# 04-ZYNQ_BANK_501.net
KiCad netlist of a schematic drawn in Altium Designer
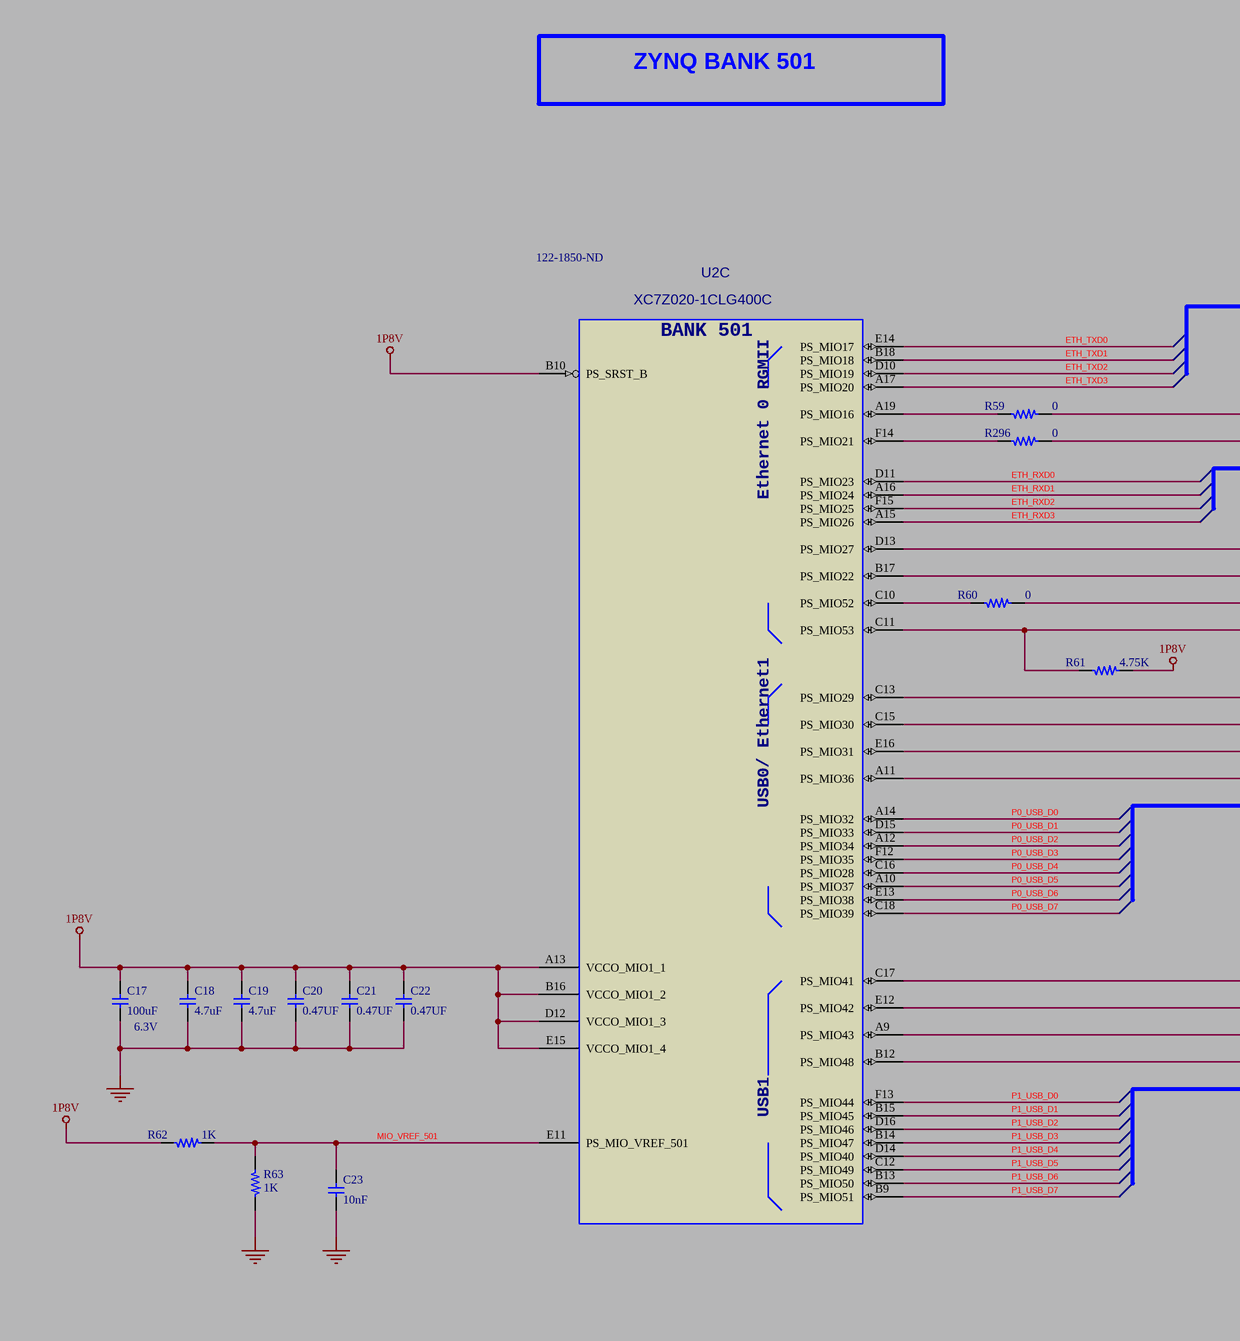
[diagram p0: 04-ZYNQ BANK 501.SchDoc, left]
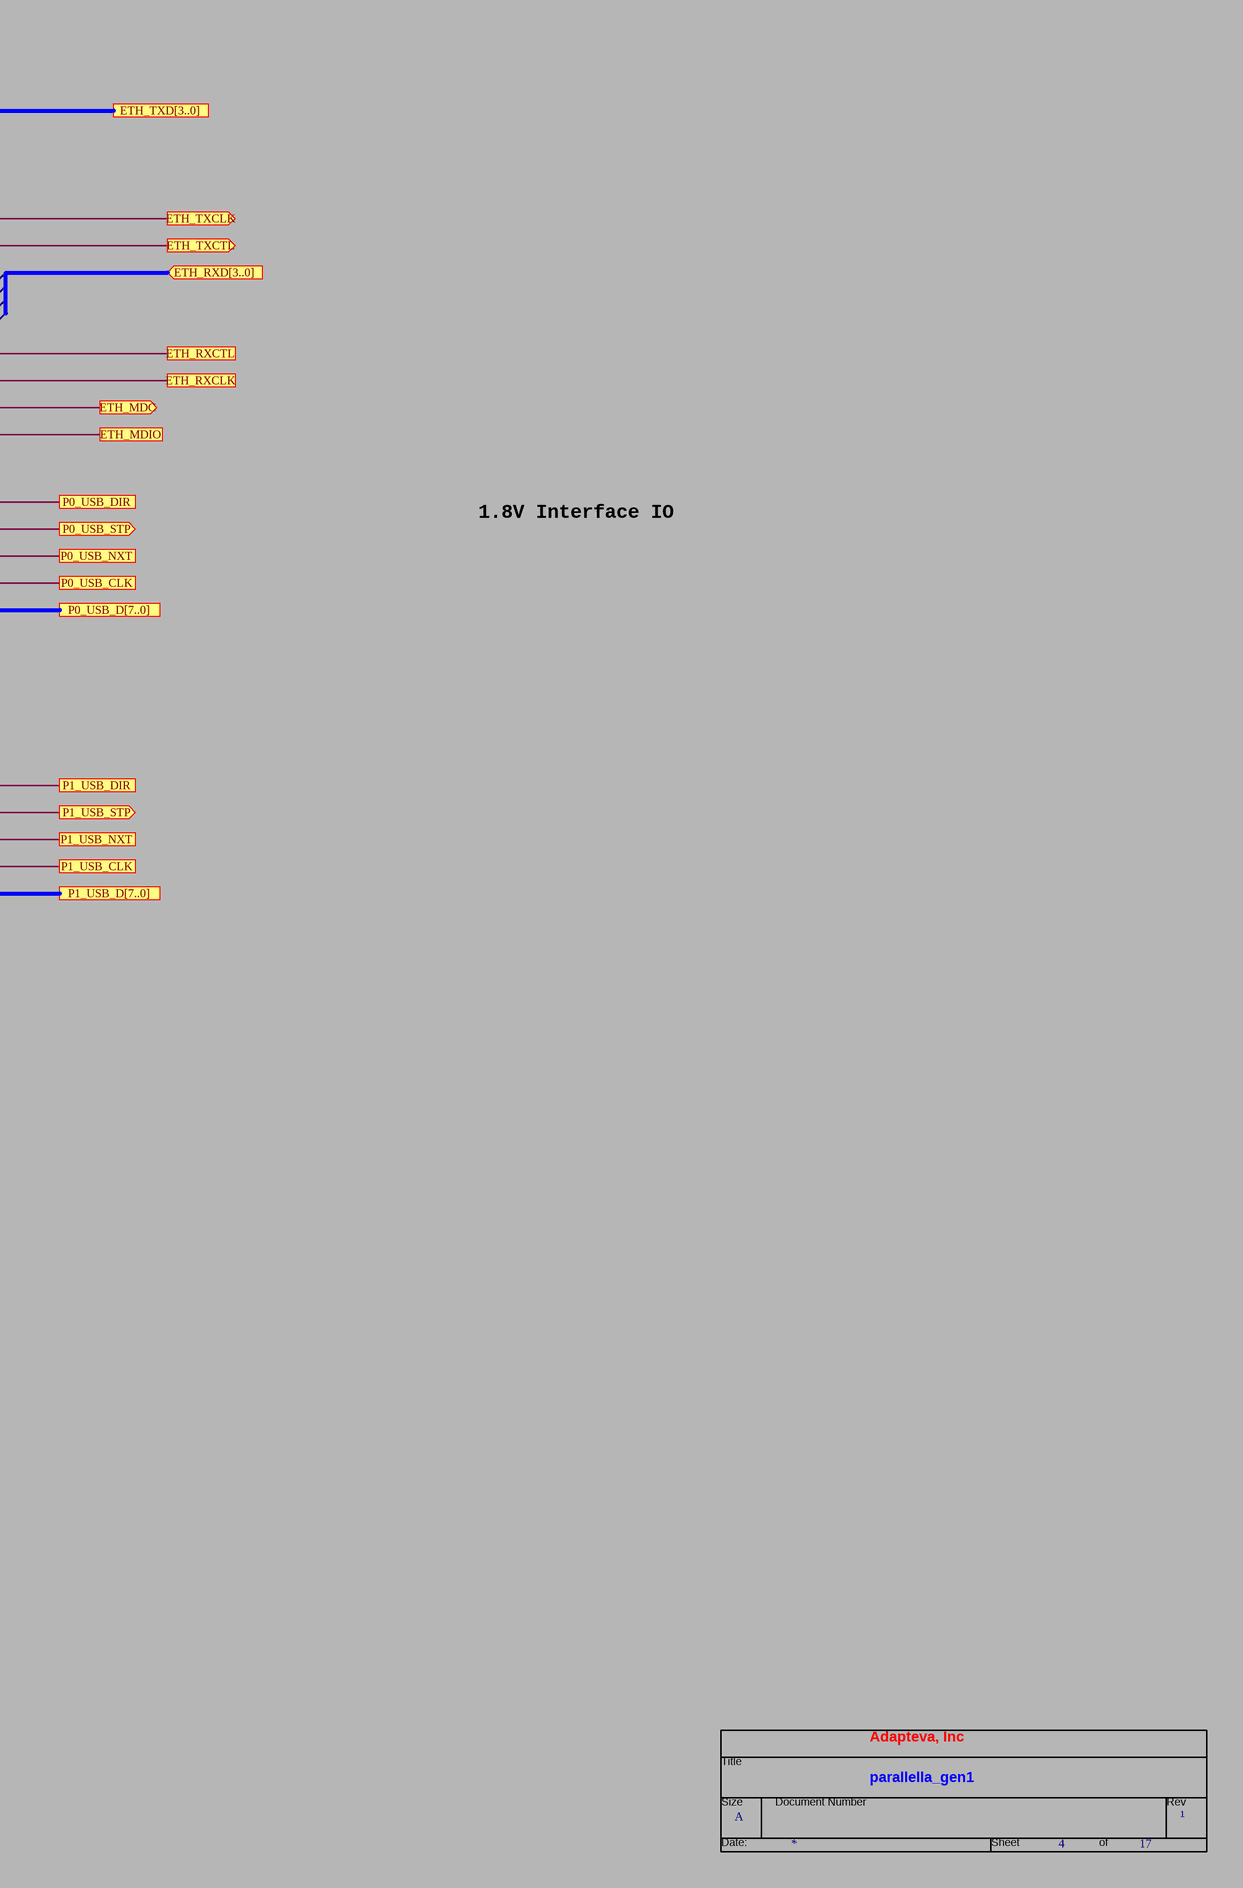
[diagram p1: 04-ZYNQ BANK 501.SchDoc, right]

(export (version "E")
  (design (tool "Eeschema 10.0.6"))
  (components
    (comp (ref "C17")
      (value "100uF")
      (footprint "C1210")
      (description "CAP, 1210, 100UF, X5R, 6.3V, LOW ESR")
      (fields
        (field (name "VOLTAGE") "6.3V")
        (field (name "MFG PART NO") "GRM32ER60J107ME20L")
        (field (name "MFG") "MURATA")
      )
      (libsource (lib "*") (part "CAP1210_100UF_X5R_LOESR"))
    )
    (comp (ref "C18")
      (value "4.7uF")
      (footprint "C0402")
      (description "CAP, 0402, 4.7UF, X5R, 6.3V")
      (fields (field (name "MFG PART NO") "C1005X5R0J475K") (field (name "MFG") "TDK"))
      (libsource (lib "*") (part "CAP0402_4P7UF_X5R"))
    )
    (comp (ref "C19")
      (value "4.7uF")
      (footprint "C0402")
      (description "CAP, 0402, 4.7UF, X5R, 6.3V")
      (fields (field (name "MFG PART NO") "C1005X5R0J475K") (field (name "MFG") "TDK"))
      (libsource (lib "*") (part "CAP0402_4P7UF_X5R"))
    )
    (comp (ref "C20")
      (value "0.47UF")
      (footprint "C0402")
      (description "CAP, 0402, 0.47UF, X5R, 16V")
      (fields (field (name "MFG") "TDK") (field (name "MFG PART NO") "C1005X5R1C474K"))
      (libsource (lib "*") (part "CAP0402_0P47UF_X5R"))
    )
    (comp (ref "C21")
      (value "0.47UF")
      (footprint "C0402")
      (description "CAP, 0402, 0.47UF, X5R, 16V")
      (fields (field (name "MFG") "TDK") (field (name "MFG PART NO") "C1005X5R1C474K"))
      (libsource (lib "*") (part "CAP0402_0P47UF_X5R"))
    )
    (comp (ref "C22")
      (value "0.47UF")
      (footprint "C0402")
      (description "CAP, 0402, 0.47UF, X5R, 16V")
      (fields (field (name "MFG") "TDK") (field (name "MFG PART NO") "C1005X5R1C474K"))
      (libsource (lib "*") (part "CAP0402_0P47UF_X5R"))
    )
    (comp (ref "C23")
      (value "10nF")
      (footprint "C0402")
      (description "CAP, 0402, 10NF, X7R, 16V")
      (fields (field (name "MFG") "TDK") (field (name "MFG PART NO") "C1005X7R1C103K"))
      (libsource (lib "*") (part "CAP0402_10NF_X7R_16V"))
    )
    (comp (ref "R59")
      (value "0")
      (footprint "R0402")
      (description "RES, 0402, 0 OHM, 1%")
      (fields (field (name "MFG") "VISHAY") (field (name "MFG PART NO") "CRCW04020000Z0ED"))
      (libsource (lib "*") (part "RES0402_0"))
    )
    (comp (ref "R60")
      (value "0")
      (footprint "R0402")
      (description "RES, 0402, 0 OHM, 1%")
      (fields (field (name "MFG") "VISHAY") (field (name "MFG PART NO") "CRCW04020000Z0ED"))
      (libsource (lib "*") (part "RES0402_0"))
    )
    (comp (ref "R61")
      (value "4.75K")
      (footprint "R0402")
      (description "RES, 0402, 4.75K, 1%")
      (fields (field (name "MFG") "VISHAY") (field (name "MFG PART NO") "CRCW04024K75FKED"))
      (libsource (lib "*") (part "RES0402_4K75"))
    )
    (comp (ref "R62")
      (value "1K")
      (footprint "R0402")
      (description "RES, 0402, 1K")
      (fields (field (name "MFG") "VISHAY") (field (name "MFG PART NO") "CRCW04021K00FKED"))
      (libsource (lib "*") (part "RES0402_1K"))
    )
    (comp (ref "R63")
      (value "1K")
      (footprint "R0402")
      (description "RES, 0402, 1K")
      (fields (field (name "MFG") "VISHAY") (field (name "MFG PART NO") "CRCW04021K00FKED"))
      (libsource (lib "*") (part "RES0402_1K"))
    )
    (comp (ref "R296")
      (value "0")
      (footprint "R0402")
      (description "RES, 0402, 0 OHM, 1%")
      (fields (field (name "MFG") "VISHAY") (field (name "MFG PART NO") "CRCW04020000Z0ED"))
      (libsource (lib "*") (part "RES0402_0"))
    )
    (comp (ref "U2")
      (value "7Z020-CLG400")
      (footprint "CBGA400_17SQ_1P6H_P8MMP")
      (description "IC, EPP, XILINX, ZYNQ, 7Z020, CLG400")
      (fields
        (field (name "VENDOR PN") "XC7Z020-1CLG400C")
        (field (name "SUPPLIER PART NUMBER 1") "122-1850-ND")
      )
      (libsource (lib "*") (part "ZYNQ_7Z020_CLG400"))
    )
  )
  (nets
    (net (code "1") (name "/ETH_MDC") (class "Default")
      (node (ref "R60") (pin "2") (pinfunction "2_2") (pintype "passive"))
    )
    (net (code "2") (name "/ETH_MDIO") (class "Default")
      (node (ref "R61") (pin "1") (pinfunction "1_1") (pintype "passive"))
      (node (ref "U2") (pin "C11") (pinfunction "PS_MIO53_C11") (pintype "bidirectional"))
    )
    (net (code "3") (name "/ETH_RXCLK") (class "Default")
      (node (ref "U2") (pin "B17") (pinfunction "PS_MIO22_B17") (pintype "bidirectional"))
    )
    (net (code "4") (name "/ETH_RXCTL") (class "Default")
      (node (ref "U2") (pin "D13") (pinfunction "PS_MIO27_D13") (pintype "bidirectional"))
    )
    (net (code "5") (name "/ETH_RXD0") (class "Default")
      (node (ref "U2") (pin "D11") (pinfunction "PS_MIO23_D11") (pintype "bidirectional"))
    )
    (net (code "6") (name "/ETH_RXD1") (class "Default")
      (node (ref "U2") (pin "A16") (pinfunction "PS_MIO24_A16") (pintype "bidirectional"))
    )
    (net (code "7") (name "/ETH_RXD2") (class "Default")
      (node (ref "U2") (pin "F15") (pinfunction "PS_MIO25_F15") (pintype "bidirectional"))
    )
    (net (code "8") (name "/ETH_RXD3") (class "Default")
      (node (ref "U2") (pin "A15") (pinfunction "PS_MIO26_A15") (pintype "bidirectional"))
    )
    (net (code "10") (name "/ETH_TXCLK") (class "Default")
      (node (ref "R59") (pin "2") (pinfunction "2_2") (pintype "passive"))
    )
    (net (code "11") (name "/ETH_TXCTL") (class "Default")
      (node (ref "R296") (pin "2") (pinfunction "2_2") (pintype "passive"))
    )
    (net (code "12") (name "/ETH_TXD0") (class "Default")
      (node (ref "U2") (pin "E14") (pinfunction "PS_MIO17_E14") (pintype "bidirectional"))
    )
    (net (code "13") (name "/ETH_TXD1") (class "Default")
      (node (ref "U2") (pin "B18") (pinfunction "PS_MIO18_B18") (pintype "bidirectional"))
    )
    (net (code "14") (name "/ETH_TXD2") (class "Default")
      (node (ref "U2") (pin "D10") (pinfunction "PS_MIO19_D10") (pintype "bidirectional"))
    )
    (net (code "15") (name "/ETH_TXD3") (class "Default")
      (node (ref "U2") (pin "A17") (pinfunction "PS_MIO20_A17") (pintype "bidirectional"))
    )
    (net (code "17") (name "/MIO_VREF_501") (class "Default")
      (node (ref "C23") (pin "1") (pinfunction "1_1") (pintype "passive"))
      (node (ref "R62") (pin "2") (pinfunction "2_2") (pintype "passive"))
      (node (ref "R63") (pin "1") (pinfunction "1_1") (pintype "passive"))
      (node (ref "U2") (pin "E11") (pinfunction "PS_MIO_VREF_501_E11") (pintype "power_in"))
    )
    (net (code "18") (name "/P0_USB_CLK") (class "Default")
      (node (ref "U2") (pin "A11") (pinfunction "PS_MIO36_A11") (pintype "bidirectional"))
    )
    (net (code "19") (name "/P0_USB_D0") (class "Default")
      (node (ref "U2") (pin "A14") (pinfunction "PS_MIO32_A14") (pintype "bidirectional"))
    )
    (net (code "20") (name "/P0_USB_D1") (class "Default")
      (node (ref "U2") (pin "D15") (pinfunction "PS_MIO33_D15") (pintype "bidirectional"))
    )
    (net (code "21") (name "/P0_USB_D2") (class "Default")
      (node (ref "U2") (pin "A12") (pinfunction "PS_MIO34_A12") (pintype "bidirectional"))
    )
    (net (code "22") (name "/P0_USB_D3") (class "Default")
      (node (ref "U2") (pin "F12") (pinfunction "PS_MIO35_F12") (pintype "bidirectional"))
    )
    (net (code "23") (name "/P0_USB_D4") (class "Default")
      (node (ref "U2") (pin "C16") (pinfunction "PS_MIO28_C16") (pintype "bidirectional"))
    )
    (net (code "24") (name "/P0_USB_D5") (class "Default")
      (node (ref "U2") (pin "A10") (pinfunction "PS_MIO37_A10") (pintype "bidirectional"))
    )
    (net (code "25") (name "/P0_USB_D6") (class "Default")
      (node (ref "U2") (pin "E13") (pinfunction "PS_MIO38_E13") (pintype "bidirectional"))
    )
    (net (code "26") (name "/P0_USB_D7") (class "Default")
      (node (ref "U2") (pin "C18") (pinfunction "PS_MIO39_C18") (pintype "bidirectional"))
    )
    (net (code "27") (name "/P0_USB_DIR") (class "Default")
      (node (ref "U2") (pin "C13") (pinfunction "PS_MIO29_C13") (pintype "bidirectional"))
    )
    (net (code "29") (name "/P0_USB_NXT") (class "Default")
      (node (ref "U2") (pin "E16") (pinfunction "PS_MIO31_E16") (pintype "bidirectional"))
    )
    (net (code "30") (name "/P0_USB_STP") (class "Default")
      (node (ref "U2") (pin "C15") (pinfunction "PS_MIO30_C15") (pintype "bidirectional"))
    )
    (net (code "31") (name "/P1_USB_CLK") (class "Default")
      (node (ref "U2") (pin "B12") (pinfunction "PS_MIO48_B12") (pintype "bidirectional"))
    )
    (net (code "32") (name "/P1_USB_D0") (class "Default")
      (node (ref "U2") (pin "F13") (pinfunction "PS_MIO44_F13") (pintype "bidirectional"))
    )
    (net (code "33") (name "/P1_USB_D1") (class "Default")
      (node (ref "U2") (pin "B15") (pinfunction "PS_MIO45_B15") (pintype "bidirectional"))
    )
    (net (code "34") (name "/P1_USB_D2") (class "Default")
      (node (ref "U2") (pin "D16") (pinfunction "PS_MIO46_D16") (pintype "bidirectional"))
    )
    (net (code "35") (name "/P1_USB_D3") (class "Default")
      (node (ref "U2") (pin "B14") (pinfunction "PS_MIO47_B14") (pintype "bidirectional"))
    )
    (net (code "36") (name "/P1_USB_D4") (class "Default")
      (node (ref "U2") (pin "D14") (pinfunction "PS_MIO40_D14") (pintype "bidirectional"))
    )
    (net (code "37") (name "/P1_USB_D5") (class "Default")
      (node (ref "U2") (pin "C12") (pinfunction "PS_MIO49_C12") (pintype "bidirectional"))
    )
    (net (code "38") (name "/P1_USB_D6") (class "Default")
      (node (ref "U2") (pin "B13") (pinfunction "PS_MIO50_B13") (pintype "bidirectional"))
    )
    (net (code "39") (name "/P1_USB_D7") (class "Default")
      (node (ref "U2") (pin "B9") (pinfunction "PS_MIO51_B9") (pintype "bidirectional"))
    )
    (net (code "40") (name "/P1_USB_DIR") (class "Default")
      (node (ref "U2") (pin "C17") (pinfunction "PS_MIO41_C17") (pintype "bidirectional"))
    )
    (net (code "42") (name "/P1_USB_NXT") (class "Default")
      (node (ref "U2") (pin "A9") (pinfunction "PS_MIO43_A9") (pintype "bidirectional"))
    )
    (net (code "43") (name "/P1_USB_STP") (class "Default")
      (node (ref "U2") (pin "E12") (pinfunction "PS_MIO42_E12") (pintype "bidirectional"))
    )
    (net (code "44") (name "1P8V") (class "Default")
      (node (ref "C17") (pin "1") (pinfunction "1_1") (pintype "passive"))
      (node (ref "C18") (pin "1") (pinfunction "1_1") (pintype "passive"))
      (node (ref "C19") (pin "1") (pinfunction "1_1") (pintype "passive"))
      (node (ref "C20") (pin "1") (pinfunction "1_1") (pintype "passive"))
      (node (ref "C21") (pin "1") (pinfunction "1_1") (pintype "passive"))
      (node (ref "C22") (pin "1") (pinfunction "1_1") (pintype "passive"))
      (node (ref "R61") (pin "2") (pinfunction "2_2") (pintype "passive"))
      (node (ref "R62") (pin "1") (pinfunction "1_1") (pintype "passive"))
      (node (ref "U2") (pin "A13") (pinfunction "VCCO_MIO1_1_A13") (pintype "power_in"))
      (node (ref "U2") (pin "B10") (pinfunction "PS_SRST_B_B10") (pintype "input"))
      (node (ref "U2") (pin "B16") (pinfunction "VCCO_MIO1_2_B16") (pintype "power_in"))
      (node (ref "U2") (pin "D12") (pinfunction "VCCO_MIO1_3_D12") (pintype "power_in"))
      (node (ref "U2") (pin "E15") (pinfunction "VCCO_MIO1_4_E15") (pintype "power_in"))
    )
    (net (code "45") (name "GND") (class "Default")
      (node (ref "C17") (pin "2") (pinfunction "2_2") (pintype "passive"))
      (node (ref "C18") (pin "2") (pinfunction "2_2") (pintype "passive"))
      (node (ref "C19") (pin "2") (pinfunction "2_2") (pintype "passive"))
      (node (ref "C20") (pin "2") (pinfunction "2_2") (pintype "passive"))
      (node (ref "C21") (pin "2") (pinfunction "2_2") (pintype "passive"))
      (node (ref "C22") (pin "2") (pinfunction "2_2") (pintype "passive"))
      (node (ref "C23") (pin "2") (pinfunction "2_2") (pintype "passive"))
      (node (ref "R63") (pin "2") (pinfunction "2_2") (pintype "passive"))
    )
    (net (code "46") (name "Net-(U2C-PS_MIO16)") (class "Default")
      (node (ref "R59") (pin "1") (pinfunction "1_1") (pintype "passive"))
      (node (ref "U2") (pin "A19") (pinfunction "PS_MIO16_A19") (pintype "bidirectional"))
    )
    (net (code "47") (name "Net-(U2C-PS_MIO21)") (class "Default")
      (node (ref "R296") (pin "1") (pinfunction "1_1") (pintype "passive"))
      (node (ref "U2") (pin "F14") (pinfunction "PS_MIO21_F14") (pintype "bidirectional"))
    )
    (net (code "48") (name "Net-(U2C-PS_MIO52)") (class "Default")
      (node (ref "R60") (pin "1") (pinfunction "1_1") (pintype "passive"))
      (node (ref "U2") (pin "C10") (pinfunction "PS_MIO52_C10") (pintype "bidirectional"))
    )
  )
)
